# complete.net
KiCad netlist of a schematic drawn in EAGLE
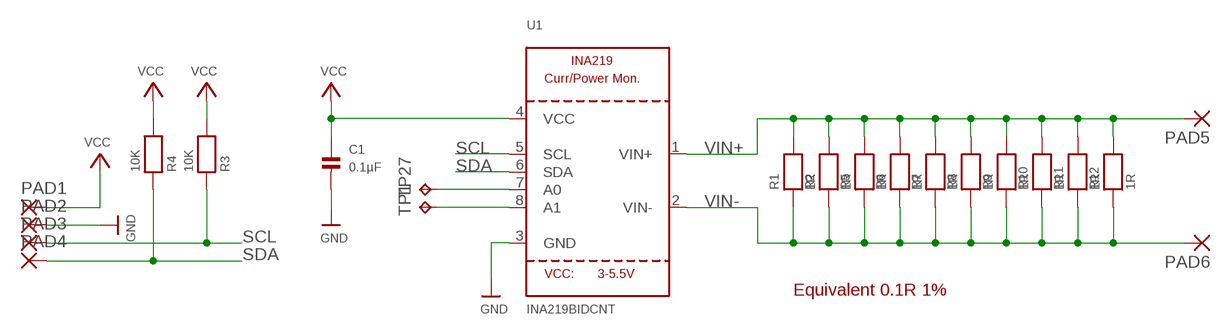
[diagram p0: schematic, sheet 1]

(export (version "E")
  (design (tool "Eeschema 10.0.6"))
  (components
    (comp (ref "C1")
      (value "0.1µF")
      (footprint "eagle-import:0805")
      (libsource (lib "eagle-import") (part "CAP_CERAMIC0805"))
    )
    (comp (ref "PAD1")
      (value "SMD2")
      (footprint "eagle-import:SMD1,27-2,54")
      (libsource (lib "eagle-import") (part "SMD2"))
    )
    (comp (ref "PAD2")
      (value "SMD2")
      (footprint "eagle-import:SMD1,27-2,54")
      (libsource (lib "eagle-import") (part "SMD2"))
    )
    (comp (ref "PAD3")
      (value "SMD2")
      (footprint "eagle-import:SMD1,27-2,54")
      (libsource (lib "eagle-import") (part "SMD2"))
    )
    (comp (ref "PAD4")
      (value "SMD2")
      (footprint "eagle-import:SMD1,27-2,54")
      (libsource (lib "eagle-import") (part "SMD2"))
    )
    (comp (ref "PAD5")
      (value "SMD2")
      (footprint "eagle-import:SMD1,27-2,54")
      (libsource (lib "eagle-import") (part "SMD2"))
    )
    (comp (ref "PAD6")
      (value "SMD2")
      (footprint "eagle-import:SMD1,27-2,54")
      (libsource (lib "eagle-import") (part "SMD2"))
    )
    (comp (ref "R1")
      (value "1R")
      (footprint "eagle-import:1206")
      (libsource (lib "eagle-import") (part "RESISTOR1206"))
    )
    (comp (ref "R2")
      (value "1R")
      (footprint "eagle-import:1206")
      (libsource (lib "eagle-import") (part "RESISTOR1206"))
    )
    (comp (ref "R3")
      (value "10K")
      (footprint "eagle-import:0805")
      (libsource (lib "eagle-import") (part "RESISTOR0805"))
    )
    (comp (ref "R4")
      (value "10K")
      (footprint "eagle-import:0805")
      (libsource (lib "eagle-import") (part "RESISTOR0805"))
    )
    (comp (ref "R5")
      (value "1R")
      (footprint "eagle-import:1206")
      (libsource (lib "eagle-import") (part "RESISTOR1206"))
    )
    (comp (ref "R6")
      (value "1R")
      (footprint "eagle-import:1206")
      (libsource (lib "eagle-import") (part "RESISTOR1206"))
    )
    (comp (ref "R7")
      (value "1R")
      (footprint "eagle-import:1206")
      (libsource (lib "eagle-import") (part "RESISTOR1206"))
    )
    (comp (ref "R8")
      (value "1R")
      (footprint "eagle-import:1206")
      (libsource (lib "eagle-import") (part "RESISTOR1206"))
    )
    (comp (ref "R9")
      (value "1R")
      (footprint "eagle-import:1206")
      (libsource (lib "eagle-import") (part "RESISTOR1206"))
    )
    (comp (ref "R10")
      (value "1R")
      (footprint "eagle-import:1206")
      (libsource (lib "eagle-import") (part "RESISTOR1206"))
    )
    (comp (ref "R11")
      (value "1R")
      (footprint "eagle-import:1206")
      (libsource (lib "eagle-import") (part "RESISTOR1206"))
    )
    (comp (ref "R12")
      (value "1R")
      (footprint "eagle-import:1206")
      (libsource (lib "eagle-import") (part "RESISTOR1206"))
    )
    (comp (ref "TP1")
      (value "TPTP06R")
      (footprint "eagle-import:TP06R")
      (libsource (lib "eagle-import") (part "TPTP06R"))
    )
    (comp (ref "TP27")
      (value "TPTP06R")
      (footprint "eagle-import:TP06R")
      (libsource (lib "eagle-import") (part "TPTP06R"))
    )
    (comp (ref "U1")
      (value "INA219BIDCNT")
      (footprint "eagle-import:SOT23-8")
      (libsource (lib "eagle-import") (part "INA219"))
    )
  )
  (nets
    (net (code "1") (name "/SCL") (class "Default")
      (node (ref "PAD3") (pin "1") (pinfunction "P_1") (pintype "passive"))
      (node (ref "R3") (pin "1") (pinfunction "1_1") (pintype "passive"))
      (node (ref "U1") (pin "5") (pinfunction "SCL_5") (pintype "bidirectional"))
    )
    (net (code "2") (name "/SDA") (class "Default")
      (node (ref "PAD4") (pin "1") (pinfunction "P_1") (pintype "passive"))
      (node (ref "R4") (pin "1") (pinfunction "1_1") (pintype "passive"))
      (node (ref "U1") (pin "6") (pinfunction "SDA_6") (pintype "bidirectional"))
    )
    (net (code "3") (name "/VIN+") (class "Default")
      (node (ref "PAD5") (pin "1") (pinfunction "P_1") (pintype "passive"))
      (node (ref "R1") (pin "2") (pinfunction "2_2") (pintype "passive"))
      (node (ref "R10") (pin "2") (pinfunction "2_2") (pintype "passive"))
      (node (ref "R11") (pin "2") (pinfunction "2_2") (pintype "passive"))
      (node (ref "R12") (pin "2") (pinfunction "2_2") (pintype "passive"))
      (node (ref "R2") (pin "2") (pinfunction "2_2") (pintype "passive"))
      (node (ref "R5") (pin "2") (pinfunction "2_2") (pintype "passive"))
      (node (ref "R6") (pin "2") (pinfunction "2_2") (pintype "passive"))
      (node (ref "R7") (pin "2") (pinfunction "2_2") (pintype "passive"))
      (node (ref "R8") (pin "2") (pinfunction "2_2") (pintype "passive"))
      (node (ref "R9") (pin "2") (pinfunction "2_2") (pintype "passive"))
      (node (ref "U1") (pin "1") (pinfunction "VIN+_1") (pintype "bidirectional"))
    )
    (net (code "4") (name "/VIN-") (class "Default")
      (node (ref "PAD6") (pin "1") (pinfunction "P_1") (pintype "passive"))
      (node (ref "R1") (pin "1") (pinfunction "1_1") (pintype "passive"))
      (node (ref "R10") (pin "1") (pinfunction "1_1") (pintype "passive"))
      (node (ref "R11") (pin "1") (pinfunction "1_1") (pintype "passive"))
      (node (ref "R12") (pin "1") (pinfunction "1_1") (pintype "passive"))
      (node (ref "R2") (pin "1") (pinfunction "1_1") (pintype "passive"))
      (node (ref "R5") (pin "1") (pinfunction "1_1") (pintype "passive"))
      (node (ref "R6") (pin "1") (pinfunction "1_1") (pintype "passive"))
      (node (ref "R7") (pin "1") (pinfunction "1_1") (pintype "passive"))
      (node (ref "R8") (pin "1") (pinfunction "1_1") (pintype "passive"))
      (node (ref "R9") (pin "1") (pinfunction "1_1") (pintype "passive"))
      (node (ref "U1") (pin "2") (pinfunction "VIN-_2") (pintype "bidirectional"))
    )
    (net (code "5") (name "GND") (class "Default")
      (node (ref "C1") (pin "2") (pinfunction "P$2_2") (pintype "passive"))
      (node (ref "PAD2") (pin "1") (pinfunction "P_1") (pintype "passive"))
      (node (ref "U1") (pin "3") (pinfunction "GND_3") (pintype "bidirectional"))
    )
    (net (code "6") (name "Net-(U1-A0)") (class "Default")
      (node (ref "TP27") (pin "TP") (pinfunction "TP_TP") (pintype "input"))
      (node (ref "U1") (pin "7") (pinfunction "A0_7") (pintype "bidirectional"))
    )
    (net (code "7") (name "Net-(U1-A1)") (class "Default")
      (node (ref "TP1") (pin "TP") (pinfunction "TP_TP") (pintype "input"))
      (node (ref "U1") (pin "8") (pinfunction "A1_8") (pintype "bidirectional"))
    )
    (net (code "8") (name "VCC") (class "Default")
      (node (ref "C1") (pin "1") (pinfunction "P$1_1") (pintype "passive"))
      (node (ref "PAD1") (pin "1") (pinfunction "P_1") (pintype "passive"))
      (node (ref "R3") (pin "2") (pinfunction "2_2") (pintype "passive"))
      (node (ref "R4") (pin "2") (pinfunction "2_2") (pintype "passive"))
      (node (ref "U1") (pin "4") (pinfunction "VCC_4") (pintype "bidirectional"))
    )
  )
)
